# BOSS-USB-Isolator.net
KiCad netlist of a schematic drawn in EAGLE
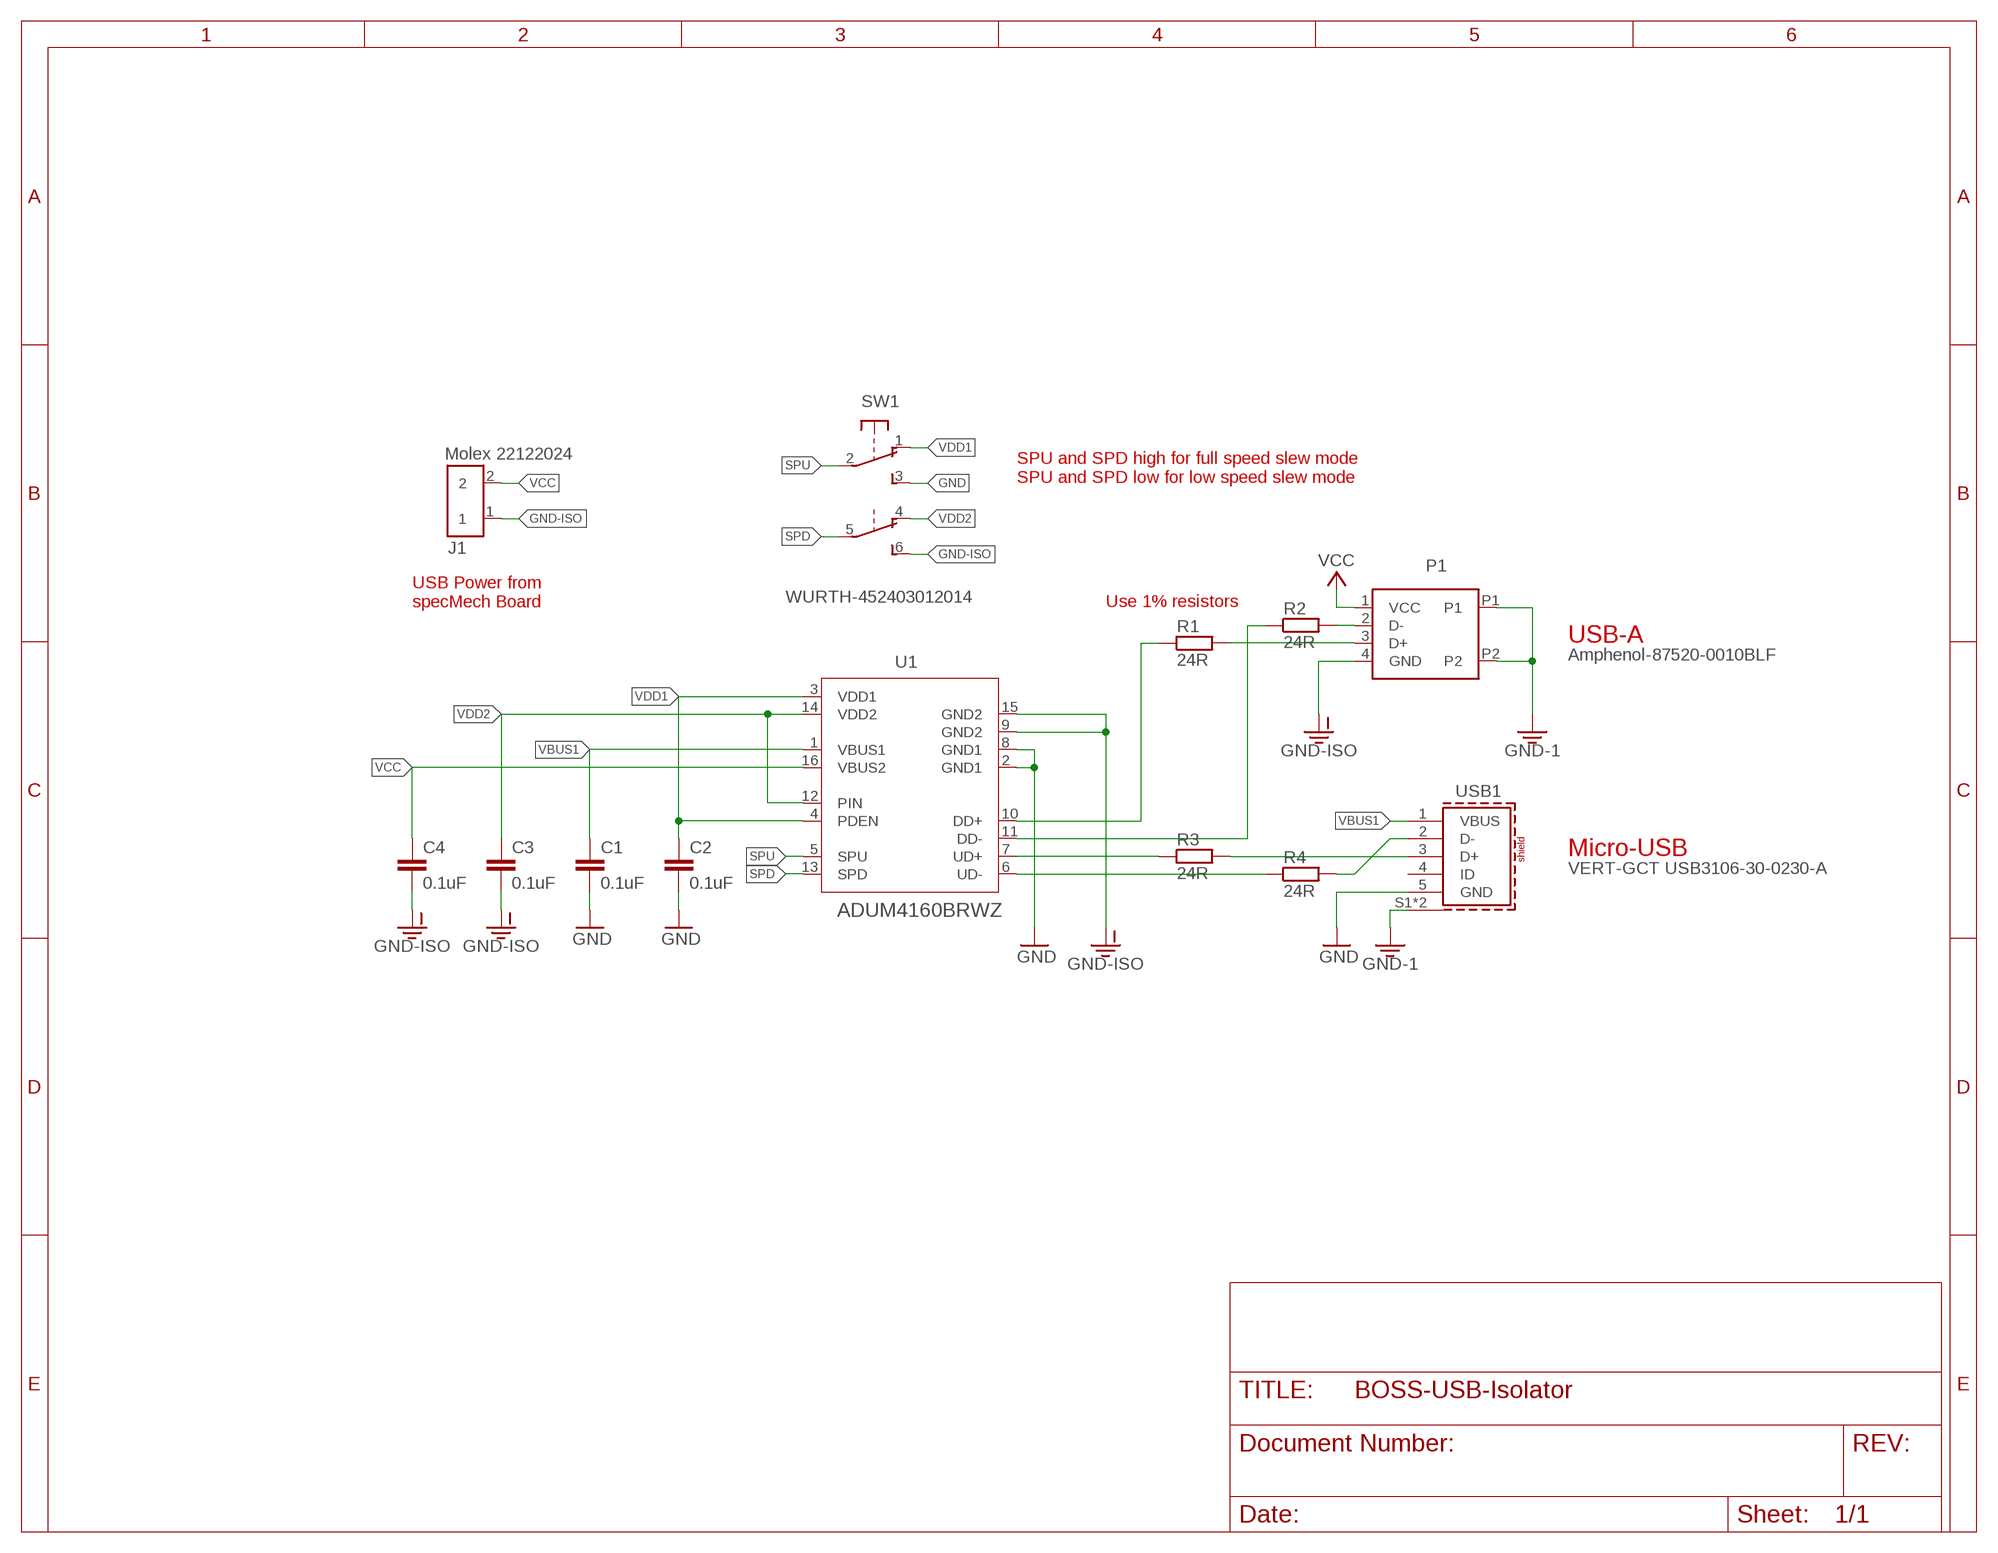
[diagram p0: schematic, sheet 1]

(export (version "E")
  (design (tool "Eeschema 10.0.6"))
  (components
    (comp (ref "C1")
      (value "0.1uF")
      (footprint "eagle-import:C0805")
      (libsource (lib "eagle-import") (part "C-EUC0805"))
    )
    (comp (ref "C2")
      (value "0.1uF")
      (footprint "eagle-import:C0805")
      (libsource (lib "eagle-import") (part "C-EUC0805"))
    )
    (comp (ref "C3")
      (value "0.1uF")
      (footprint "eagle-import:C0805")
      (libsource (lib "eagle-import") (part "C-EUC0805"))
    )
    (comp (ref "C4")
      (value "0.1uF")
      (footprint "eagle-import:C0805")
      (libsource (lib "eagle-import") (part "C-EUC0805"))
    )
    (comp (ref "J1")
      (value "Molex 22122024")
      (footprint "eagle-import:1X02RA-MOLEX-22122024")
      (libsource (lib "eagle-import") (part "PINHD-1X2RA-MOLEX-22122024MOLEX-22122024"))
    )
    (comp (ref "P1")
      (value "Amphenol-87520-0010BLF")
      (footprint "eagle-import:FCI_87520-0010BLF")
      (fields
        (field (name "DIGI-KEY_PART_NUMBER") "609-1045-ND")
        (field (name "MF") "Amphenol ICC")
        (field (name "MP") "87520-0010BLF")
      )
      (libsource (lib "eagle-import") (part "USBA-87520-0010BLF"))
    )
    (comp (ref "R1")
      (value "24R")
      (footprint "eagle-import:R0805")
      (libsource (lib "eagle-import") (part "R-EU_R0805"))
    )
    (comp (ref "R2")
      (value "24R")
      (footprint "eagle-import:R0805")
      (libsource (lib "eagle-import") (part "R-EU_R0805"))
    )
    (comp (ref "R3")
      (value "24R")
      (footprint "eagle-import:R0805")
      (libsource (lib "eagle-import") (part "R-EU_R0805"))
    )
    (comp (ref "R4")
      (value "24R")
      (footprint "eagle-import:R0805")
      (libsource (lib "eagle-import") (part "R-EU_R0805"))
    )
    (comp (ref "SW1")
      (value "WURTH-452403012014")
      (footprint "eagle-import:WS-SLSV")
      (libsource (lib "eagle-import") (part "DPDT-WURTH-WS-SLSV"))
    )
    (comp (ref "U1")
      (value "ADUM4160BRWZ")
      (footprint "eagle-import:RW_16_ADI")
      (libsource (lib "eagle-import") (part "ADUM4160BRWZ"))
    )
    (comp (ref "USB1")
      (value "VERT-GCT USB3106-30-0230-A")
      (footprint "eagle-import:USB-VERT-GCT-USB3106-30-0230-A")
      (libsource (lib "eagle-import") (part "USB-VERT-GCT"))
    )
  )
  (nets
    (net (code "1") (name "GND") (class "Default")
      (node (ref "C1") (pin "2") (pinfunction "2_2") (pintype "passive"))
      (node (ref "C2") (pin "2") (pinfunction "2_2") (pintype "passive"))
      (node (ref "SW1") (pin "3") (pinfunction "3_3") (pintype "passive"))
      (node (ref "U1") (pin "2") (pinfunction "GND1_2") (pintype "passive"))
      (node (ref "U1") (pin "8") (pinfunction "GND1_8") (pintype "passive"))
      (node (ref "USB1") (pin "5") (pinfunction "GND_5") (pintype "passive"))
    )
    (net (code "2") (name "GND-1") (class "Default")
      (node (ref "P1") (pin "P1") (pinfunction "P1_P1") (pintype "bidirectional"))
      (node (ref "P1") (pin "P2") (pinfunction "P2_P2") (pintype "bidirectional"))
      (node (ref "USB1") (pin "S1") (pinfunction "SHIELD_S1") (pintype "passive"))
      (node (ref "USB1") (pin "S2") (pinfunction "SHIELD_S2") (pintype "passive"))
    )
    (net (code "3") (name "GND-ISO") (class "Default")
      (node (ref "C3") (pin "2") (pinfunction "2_2") (pintype "passive"))
      (node (ref "C4") (pin "2") (pinfunction "2_2") (pintype "passive"))
      (node (ref "J1") (pin "1") (pinfunction "1_1") (pintype "bidirectional"))
      (node (ref "P1") (pin "4") (pinfunction "GND_4") (pintype "power_in"))
      (node (ref "SW1") (pin "6") (pinfunction "6_6") (pintype "passive"))
      (node (ref "U1") (pin "15") (pinfunction "GND2_15") (pintype "passive"))
      (node (ref "U1") (pin "9") (pinfunction "GND2_9") (pintype "passive"))
    )
    (net (code "4") (name "Net-(P1-D+)") (class "Default")
      (node (ref "P1") (pin "3") (pinfunction "D+_3") (pintype "bidirectional"))
      (node (ref "R1") (pin "2") (pinfunction "2_2") (pintype "passive"))
    )
    (net (code "5") (name "Net-(P1-D-)") (class "Default")
      (node (ref "P1") (pin "2") (pinfunction "D-_2") (pintype "bidirectional"))
      (node (ref "R2") (pin "2") (pinfunction "2_2") (pintype "passive"))
    )
    (net (code "6") (name "Net-(U1-DD+)") (class "Default")
      (node (ref "R1") (pin "1") (pinfunction "1_1") (pintype "passive"))
      (node (ref "U1") (pin "10") (pinfunction "DD+_10") (pintype "passive"))
    )
    (net (code "7") (name "Net-(U1-DD-)") (class "Default")
      (node (ref "R2") (pin "1") (pinfunction "1_1") (pintype "passive"))
      (node (ref "U1") (pin "11") (pinfunction "DD-_11") (pintype "passive"))
    )
    (net (code "8") (name "Net-(U1-UD+)") (class "Default")
      (node (ref "R3") (pin "1") (pinfunction "1_1") (pintype "passive"))
      (node (ref "U1") (pin "7") (pinfunction "UD+_7") (pintype "passive"))
    )
    (net (code "9") (name "Net-(U1-UD-)") (class "Default")
      (node (ref "R4") (pin "1") (pinfunction "1_1") (pintype "passive"))
      (node (ref "U1") (pin "6") (pinfunction "UD-_6") (pintype "passive"))
    )
    (net (code "10") (name "Net-(USB1-D+)") (class "Default")
      (node (ref "R3") (pin "2") (pinfunction "2_2") (pintype "passive"))
      (node (ref "USB1") (pin "3") (pinfunction "D+_3") (pintype "passive"))
    )
    (net (code "11") (name "Net-(USB1-D-)") (class "Default")
      (node (ref "R4") (pin "2") (pinfunction "2_2") (pintype "passive"))
      (node (ref "USB1") (pin "2") (pinfunction "D-_2") (pintype "passive"))
    )
    (net (code "12") (name "SPD") (class "Default")
      (node (ref "SW1") (pin "5") (pinfunction "5_5") (pintype "passive"))
      (node (ref "U1") (pin "13") (pinfunction "SPD_13") (pintype "passive"))
    )
    (net (code "13") (name "SPU") (class "Default")
      (node (ref "SW1") (pin "2") (pinfunction "2_2") (pintype "passive"))
      (node (ref "U1") (pin "5") (pinfunction "SPU_5") (pintype "passive"))
    )
    (net (code "14") (name "VBUS1") (class "Default")
      (node (ref "C1") (pin "1") (pinfunction "1_1") (pintype "passive"))
      (node (ref "U1") (pin "1") (pinfunction "VBUS1_1") (pintype "passive"))
      (node (ref "USB1") (pin "1") (pinfunction "VBUS_1") (pintype "passive"))
    )
    (net (code "15") (name "VCC") (class "Default")
      (node (ref "C4") (pin "1") (pinfunction "1_1") (pintype "passive"))
      (node (ref "J1") (pin "2") (pinfunction "2_2") (pintype "bidirectional"))
      (node (ref "P1") (pin "1") (pinfunction "VCC_1") (pintype "power_in"))
      (node (ref "U1") (pin "16") (pinfunction "VBUS2_16") (pintype "passive"))
    )
    (net (code "16") (name "VDD1") (class "Default")
      (node (ref "C2") (pin "1") (pinfunction "1_1") (pintype "passive"))
      (node (ref "SW1") (pin "1") (pinfunction "1_1") (pintype "passive"))
      (node (ref "U1") (pin "3") (pinfunction "VDD1_3") (pintype "passive"))
      (node (ref "U1") (pin "4") (pinfunction "PDEN_4") (pintype "passive"))
    )
    (net (code "17") (name "VDD2") (class "Default")
      (node (ref "C3") (pin "1") (pinfunction "1_1") (pintype "passive"))
      (node (ref "SW1") (pin "4") (pinfunction "4_4") (pintype "passive"))
      (node (ref "U1") (pin "12") (pinfunction "PIN_12") (pintype "passive"))
      (node (ref "U1") (pin "14") (pinfunction "VDD2_14") (pintype "passive"))
    )
    (net (code "18") (name "unconnected-(USB1-ID-Pad4)") (class "Default")
      (node (ref "USB1") (pin "4") (pinfunction "ID_4") (pintype "passive"))
    )
  )
)
